# GenericPiHAT_06-1_0.net
KiCad netlist of a schematic drawn in Altium Designer
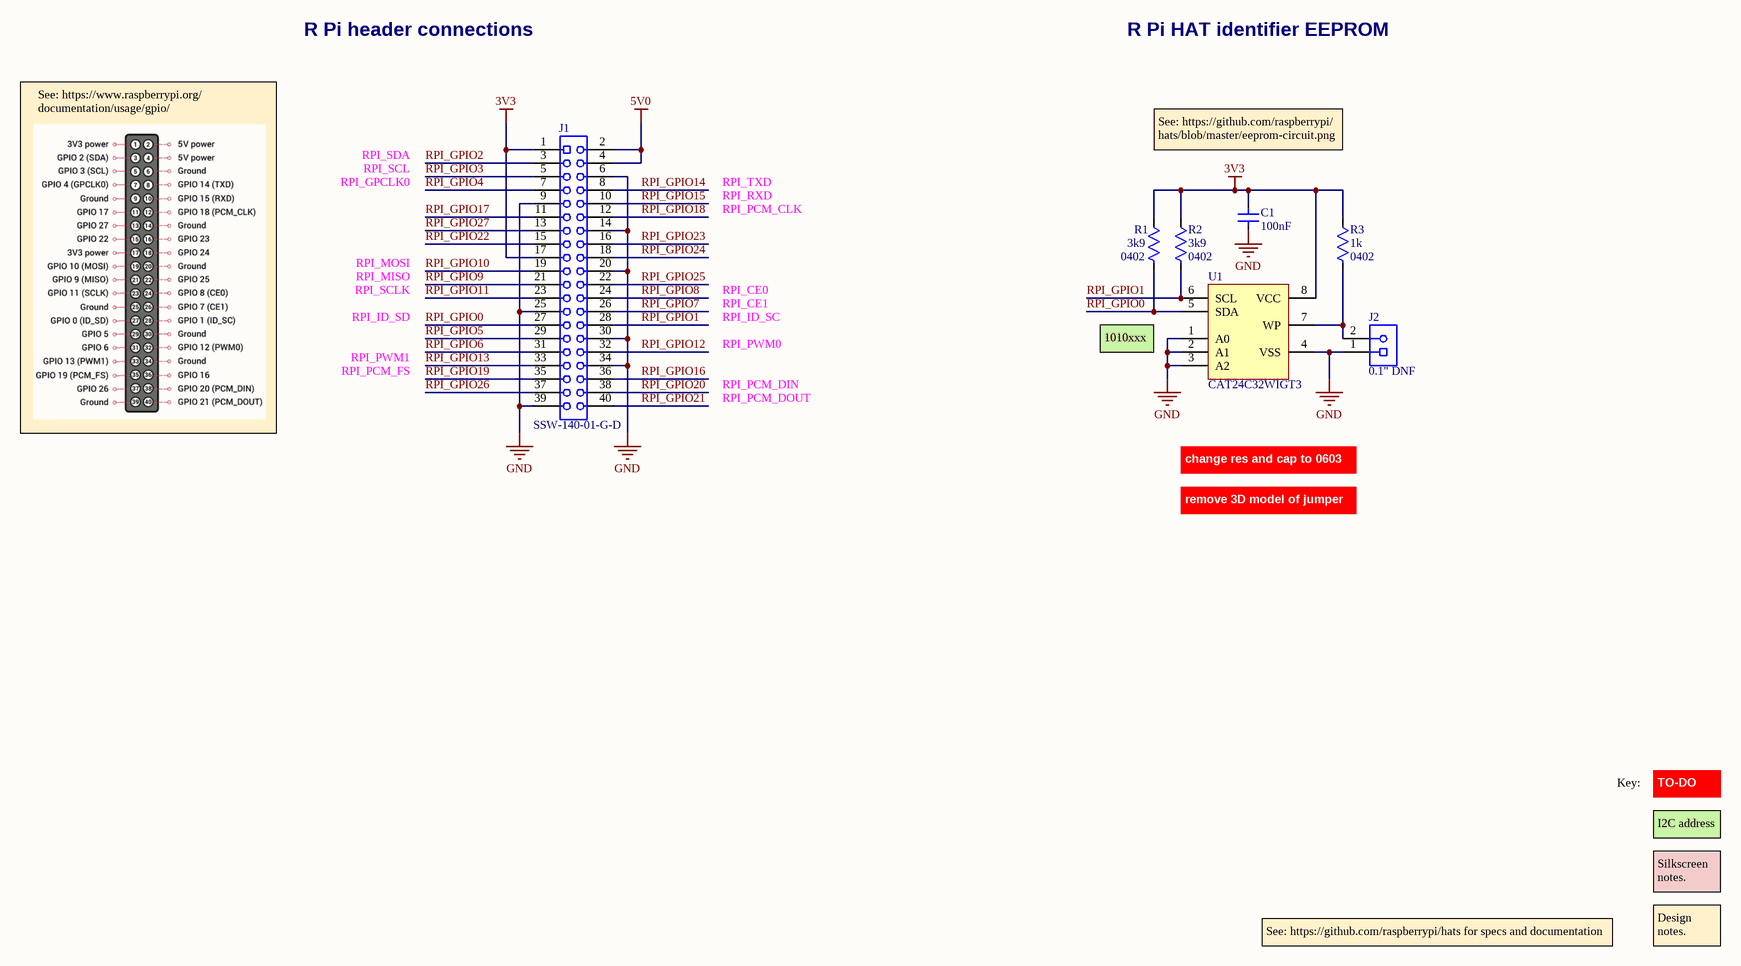
[diagram p0: GenericPiHAT 06-1.0.SchDoc]

(export (version "E")
  (design (tool "Eeschema 10.0.6"))
  (components
    (comp (ref "C1")
      (value "100nF")
      (footprint "TDK 2010")
      (description "CAP CER 0.1UF 10V X5R 0201")
      (fields
        (field (name "MANUFACTURER") "TDK Corporation")
        (field (name "MANUFACTURER PART NUMBER") "C0603X5R1A104K030BC")
      )
      (libsource (lib "TDK_Capacitor_C_0201") (part "100nF 0201 10V"))
    )
    (comp (ref "J1")
      (value "SSW-140-01-G-D")
      (footprint "SSW-140-01-G-D")
      (description "CONN RCPT .100\" 40POS DUAL")
      (fields
        (field (name "MANUFACTURER") "Samtec")
        (field (name "MANUFACTURER PART NUMBER") "SSW-140-01-G-D")
      )
      (libsource (lib "Samtec") (part "SSW-140-01-G-D"))
    )
    (comp (ref "J2")
      (value "0.1\" DNF")
      (footprint "Generic 1x2 2.54mm header")
      (description "2.54mm, 2x1 way, vertical, square pin, gold plate")
      (fields (field (name "MANUFACTURER") "MULTICOMP") (field (name "MANUFACTURER PART NUMBER") "2211S-02G"))
      (libsource (lib "generic-con") (part "Header Multicomp 2211S-02G-whitesch"))
    )
    (comp (ref "R1")
      (value "3k9")
      (footprint "RES0402")
      (description "Generic 0402 Chip Resistor 3k9")
      (fields (field (name "CASE") "0402"))
      (libsource (lib "generic-res") (part "RES0402_GENERIC"))
    )
    (comp (ref "R2")
      (value "3k9")
      (footprint "RES0402")
      (description "Generic 0402 Chip Resistor 3k9")
      (fields (field (name "CASE") "0402"))
      (libsource (lib "generic-res") (part "RES0402_GENERIC"))
    )
    (comp (ref "R3")
      (value "1k")
      (footprint "RES0402")
      (description "Generic 0402 Chip Resistor 1k")
      (fields (field (name "CASE") "0402"))
      (libsource (lib "generic-res") (part "RES0402_GENERIC"))
    )
    (comp (ref "U1")
      (value "CAT24C32WI-GT3")
      (footprint "ONSC-SOIC-8-751BD-01_L")
      (fields
        (field (name "MANUFACTURER") "ON Semiconductor")
        (field (name "MANUFACTURER PART NUMBER") "CAT24C32WIGT3")
      )
      (libsource (lib "OnSemiconductor") (part "CAT24C32WI-GT3"))
    )
  )
  (nets
    (net (code "1") (name "/RPI_GPIO0") (class "Default")
      (node (ref "J1") (pin "27") (pinfunction "27_27") (pintype "passive"))
      (node (ref "R1") (pin "2") (pinfunction "2_2") (pintype "passive"))
      (node (ref "U1") (pin "5") (pinfunction "SDA_5") (pintype "passive"))
    )
    (net (code "2") (name "/RPI_GPIO1") (class "Default")
      (node (ref "J1") (pin "28") (pinfunction "28_28") (pintype "passive"))
      (node (ref "R2") (pin "2") (pinfunction "2_2") (pintype "passive"))
      (node (ref "U1") (pin "6") (pinfunction "SCL_6") (pintype "passive"))
    )
    (net (code "3") (name "/RPI_GPIO2") (class "Default")
      (node (ref "J1") (pin "3") (pinfunction "3_3") (pintype "passive"))
    )
    (net (code "4") (name "/RPI_GPIO3") (class "Default")
      (node (ref "J1") (pin "5") (pinfunction "5_5") (pintype "passive"))
    )
    (net (code "5") (name "/RPI_GPIO4") (class "Default")
      (node (ref "J1") (pin "7") (pinfunction "7_7") (pintype "passive"))
    )
    (net (code "6") (name "/RPI_GPIO5") (class "Default")
      (node (ref "J1") (pin "29") (pinfunction "29_29") (pintype "passive"))
    )
    (net (code "7") (name "/RPI_GPIO6") (class "Default")
      (node (ref "J1") (pin "31") (pinfunction "31_31") (pintype "passive"))
    )
    (net (code "8") (name "/RPI_GPIO7") (class "Default")
      (node (ref "J1") (pin "26") (pinfunction "26_26") (pintype "passive"))
    )
    (net (code "9") (name "/RPI_GPIO8") (class "Default")
      (node (ref "J1") (pin "24") (pinfunction "24_24") (pintype "passive"))
    )
    (net (code "10") (name "/RPI_GPIO9") (class "Default")
      (node (ref "J1") (pin "21") (pinfunction "21_21") (pintype "passive"))
    )
    (net (code "11") (name "/RPI_GPIO10") (class "Default")
      (node (ref "J1") (pin "19") (pinfunction "19_19") (pintype "passive"))
    )
    (net (code "12") (name "/RPI_GPIO11") (class "Default")
      (node (ref "J1") (pin "23") (pinfunction "23_23") (pintype "passive"))
    )
    (net (code "13") (name "/RPI_GPIO12") (class "Default")
      (node (ref "J1") (pin "32") (pinfunction "32_32") (pintype "passive"))
    )
    (net (code "14") (name "/RPI_GPIO13") (class "Default")
      (node (ref "J1") (pin "33") (pinfunction "33_33") (pintype "passive"))
    )
    (net (code "15") (name "/RPI_GPIO14") (class "Default")
      (node (ref "J1") (pin "8") (pinfunction "8_8") (pintype "passive"))
    )
    (net (code "16") (name "/RPI_GPIO15") (class "Default")
      (node (ref "J1") (pin "10") (pinfunction "10_10") (pintype "passive"))
    )
    (net (code "17") (name "/RPI_GPIO16") (class "Default")
      (node (ref "J1") (pin "36") (pinfunction "36_36") (pintype "passive"))
    )
    (net (code "18") (name "/RPI_GPIO17") (class "Default")
      (node (ref "J1") (pin "11") (pinfunction "11_11") (pintype "passive"))
    )
    (net (code "19") (name "/RPI_GPIO18") (class "Default")
      (node (ref "J1") (pin "12") (pinfunction "12_12") (pintype "passive"))
    )
    (net (code "20") (name "/RPI_GPIO19") (class "Default")
      (node (ref "J1") (pin "35") (pinfunction "35_35") (pintype "passive"))
    )
    (net (code "21") (name "/RPI_GPIO20") (class "Default")
      (node (ref "J1") (pin "38") (pinfunction "38_38") (pintype "passive"))
    )
    (net (code "22") (name "/RPI_GPIO21") (class "Default")
      (node (ref "J1") (pin "40") (pinfunction "40_40") (pintype "passive"))
    )
    (net (code "23") (name "/RPI_GPIO22") (class "Default")
      (node (ref "J1") (pin "15") (pinfunction "15_15") (pintype "passive"))
    )
    (net (code "24") (name "/RPI_GPIO23") (class "Default")
      (node (ref "J1") (pin "16") (pinfunction "16_16") (pintype "passive"))
    )
    (net (code "25") (name "/RPI_GPIO24") (class "Default")
      (node (ref "J1") (pin "18") (pinfunction "18_18") (pintype "passive"))
    )
    (net (code "26") (name "/RPI_GPIO25") (class "Default")
      (node (ref "J1") (pin "22") (pinfunction "22_22") (pintype "passive"))
    )
    (net (code "27") (name "/RPI_GPIO26") (class "Default")
      (node (ref "J1") (pin "37") (pinfunction "37_37") (pintype "passive"))
    )
    (net (code "28") (name "/RPI_GPIO27") (class "Default")
      (node (ref "J1") (pin "13") (pinfunction "13_13") (pintype "passive"))
    )
    (net (code "29") (name "3V3") (class "Default")
      (node (ref "C1") (pin "2") (pinfunction "2_2") (pintype "passive"))
      (node (ref "J1") (pin "1") (pinfunction "1_1") (pintype "passive"))
      (node (ref "J1") (pin "17") (pinfunction "17_17") (pintype "passive"))
      (node (ref "R1") (pin "1") (pinfunction "1_1") (pintype "passive"))
      (node (ref "R2") (pin "1") (pinfunction "1_1") (pintype "passive"))
      (node (ref "R3") (pin "1") (pinfunction "1_1") (pintype "passive"))
      (node (ref "U1") (pin "8") (pinfunction "VCC_8") (pintype "passive"))
    )
    (net (code "30") (name "5V0") (class "Default")
      (node (ref "J1") (pin "2") (pinfunction "2_2") (pintype "passive"))
      (node (ref "J1") (pin "4") (pinfunction "4_4") (pintype "passive"))
    )
    (net (code "31") (name "GND") (class "Default")
      (node (ref "C1") (pin "1") (pinfunction "1_1") (pintype "passive"))
      (node (ref "J1") (pin "14") (pinfunction "14_14") (pintype "passive"))
      (node (ref "J1") (pin "20") (pinfunction "20_20") (pintype "passive"))
      (node (ref "J1") (pin "25") (pinfunction "25_25") (pintype "passive"))
      (node (ref "J1") (pin "30") (pinfunction "30_30") (pintype "passive"))
      (node (ref "J1") (pin "34") (pinfunction "34_34") (pintype "passive"))
      (node (ref "J1") (pin "39") (pinfunction "39_39") (pintype "passive"))
      (node (ref "J1") (pin "6") (pinfunction "6_6") (pintype "passive"))
      (node (ref "J1") (pin "9") (pinfunction "9_9") (pintype "passive"))
      (node (ref "J2") (pin "1") (pinfunction "1_1") (pintype "passive"))
      (node (ref "U1") (pin "1") (pinfunction "A0_1") (pintype "passive"))
      (node (ref "U1") (pin "2") (pinfunction "A1_2") (pintype "passive"))
      (node (ref "U1") (pin "3") (pinfunction "A2_3") (pintype "passive"))
      (node (ref "U1") (pin "4") (pinfunction "VSS_4") (pintype "passive"))
    )
    (net (code "32") (name "Net-(U1-WP)") (class "Default")
      (node (ref "J2") (pin "2") (pinfunction "2_2") (pintype "passive"))
      (node (ref "R3") (pin "2") (pinfunction "2_2") (pintype "passive"))
      (node (ref "U1") (pin "7") (pinfunction "WP_7") (pintype "passive"))
    )
  )
)
